# Mabee_WS2812_8bit_V1_1.net
KiCad netlist of a schematic drawn in EAGLE
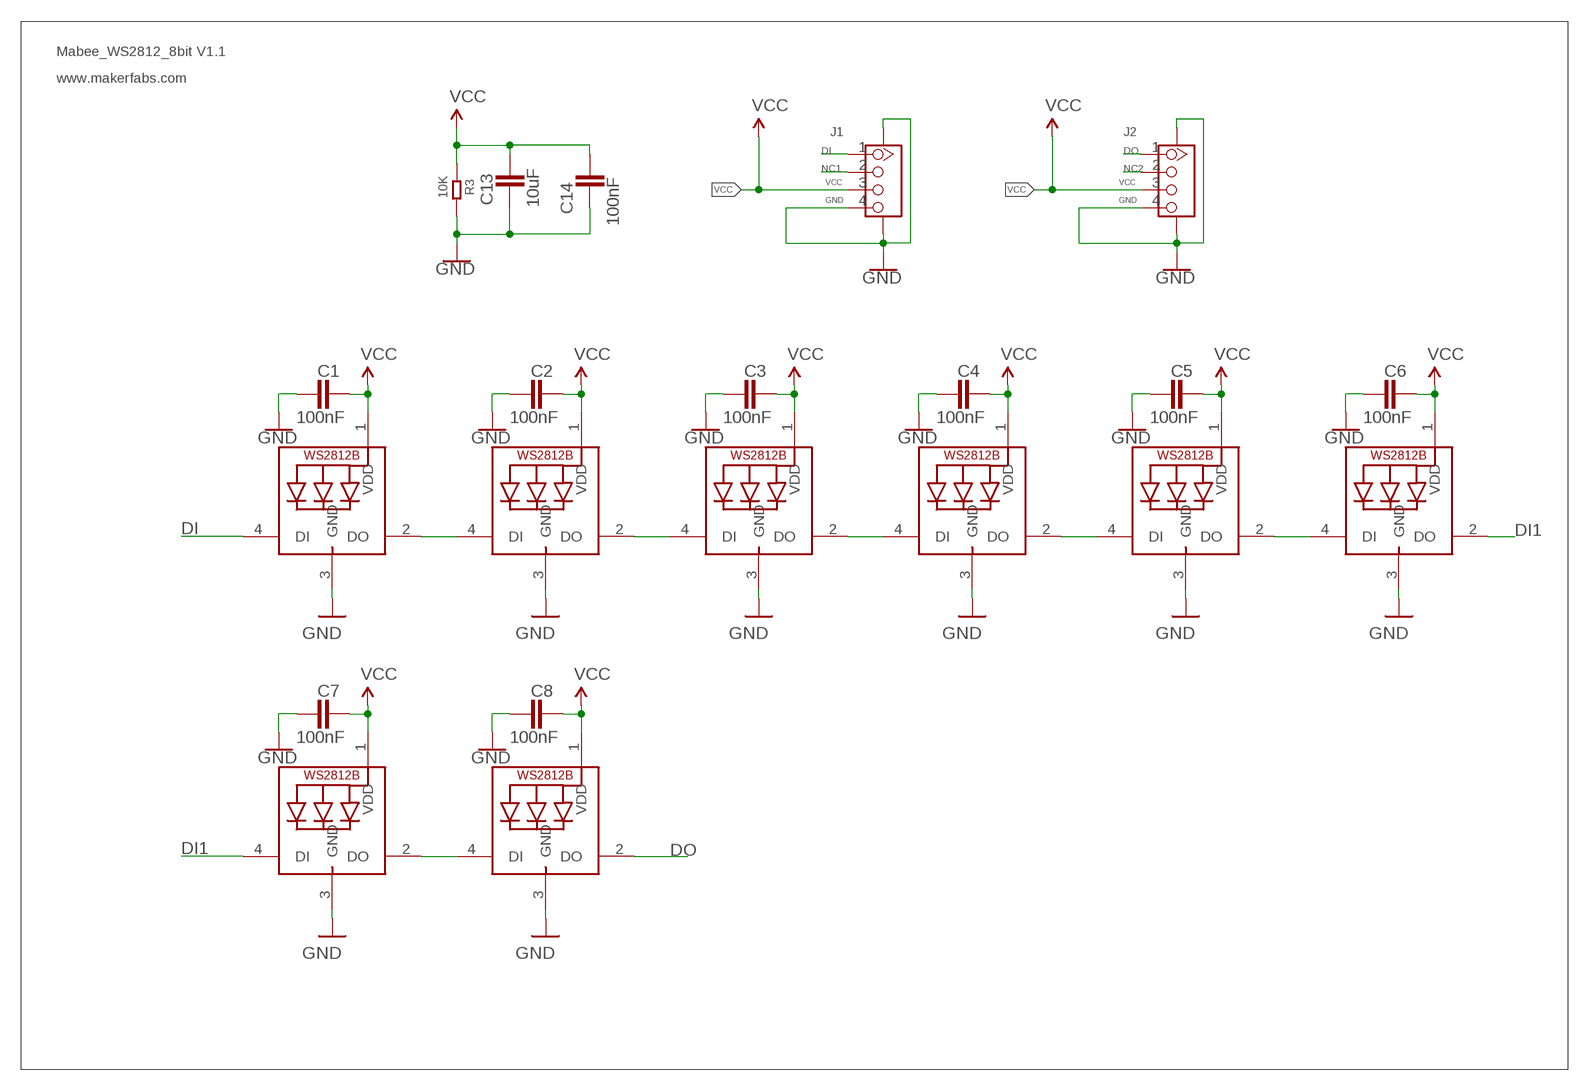
[diagram p0: schematic, sheet 1]

(export (version "E")
  (design (tool "Eeschema 10.0.6"))
  (components
    (comp (ref "C1")
      (value "100nF")
      (footprint "eagle-import:C0603")
      (libsource (lib "eagle-import") (part "C-EUC0603"))
    )
    (comp (ref "C2")
      (value "100nF")
      (footprint "eagle-import:C0603")
      (libsource (lib "eagle-import") (part "C-EUC0603"))
    )
    (comp (ref "C3")
      (value "100nF")
      (footprint "eagle-import:C0603")
      (libsource (lib "eagle-import") (part "C-EUC0603"))
    )
    (comp (ref "C4")
      (value "100nF")
      (footprint "eagle-import:C0603")
      (libsource (lib "eagle-import") (part "C-EUC0603"))
    )
    (comp (ref "C5")
      (value "100nF")
      (footprint "eagle-import:C0603")
      (libsource (lib "eagle-import") (part "C-EUC0603"))
    )
    (comp (ref "C6")
      (value "100nF")
      (footprint "eagle-import:C0603")
      (libsource (lib "eagle-import") (part "C-EUC0603"))
    )
    (comp (ref "C7")
      (value "100nF")
      (footprint "eagle-import:C0603")
      (libsource (lib "eagle-import") (part "C-EUC0603"))
    )
    (comp (ref "C8")
      (value "100nF")
      (footprint "eagle-import:C0603")
      (libsource (lib "eagle-import") (part "C-EUC0603"))
    )
    (comp (ref "C13")
      (value "10uF")
      (footprint "eagle-import:C0603")
      (libsource (lib "eagle-import") (part "C-EUC0603"))
    )
    (comp (ref "C14")
      (value "100nF")
      (footprint "eagle-import:C0603")
      (libsource (lib "eagle-import") (part "C-EUC0603"))
    )
    (comp (ref "J1")
      (value "GROVE-CONNECTOR-SMD'90D'")
      (footprint "eagle-import:HW4-SMD-2.0-90D")
      (libsource (lib "eagle-import") (part "GROVE-CONNECTOR-SMD'90D'"))
    )
    (comp (ref "J2")
      (value "GROVE-CONNECTOR-SMD'90D'")
      (footprint "eagle-import:HW4-SMD-2.0-90D")
      (libsource (lib "eagle-import") (part "GROVE-CONNECTOR-SMD'90D'"))
    )
    (comp (ref "LED0")
      (value "WS2812B3535")
      (footprint "eagle-import:LED3535")
      (libsource (lib "eagle-import") (part "WS2812B3535"))
    )
    (comp (ref "LED1")
      (value "WS2812B3535")
      (footprint "eagle-import:LED3535")
      (libsource (lib "eagle-import") (part "WS2812B3535"))
    )
    (comp (ref "LED2")
      (value "WS2812B3535")
      (footprint "eagle-import:LED3535")
      (libsource (lib "eagle-import") (part "WS2812B3535"))
    )
    (comp (ref "LED3")
      (value "WS2812B3535")
      (footprint "eagle-import:LED3535")
      (libsource (lib "eagle-import") (part "WS2812B3535"))
    )
    (comp (ref "LED4")
      (value "WS2812B3535")
      (footprint "eagle-import:LED3535")
      (libsource (lib "eagle-import") (part "WS2812B3535"))
    )
    (comp (ref "LED5")
      (value "WS2812B3535")
      (footprint "eagle-import:LED3535")
      (libsource (lib "eagle-import") (part "WS2812B3535"))
    )
    (comp (ref "LED6")
      (value "WS2812B3535")
      (footprint "eagle-import:LED3535")
      (libsource (lib "eagle-import") (part "WS2812B3535"))
    )
    (comp (ref "LED7")
      (value "WS2812B3535")
      (footprint "eagle-import:LED3535")
      (libsource (lib "eagle-import") (part "WS2812B3535"))
    )
    (comp (ref "R3")
      (value "10K")
      (footprint "eagle-import:R0603")
      (libsource (lib "eagle-import") (part "R-0603"))
    )
  )
  (nets
    (net (code "1") (name "/DI") (class "Default")
      (node (ref "J1") (pin "1") (pinfunction "1_1") (pintype "bidirectional"))
      (node (ref "LED0") (pin "4") (pinfunction "DI_4") (pintype "input"))
    )
    (net (code "2") (name "/DI1") (class "Default")
      (node (ref "LED5") (pin "2") (pinfunction "DO_2") (pintype "output"))
      (node (ref "LED6") (pin "4") (pinfunction "DI_4") (pintype "input"))
    )
    (net (code "3") (name "/DO") (class "Default")
      (node (ref "J2") (pin "1") (pinfunction "1_1") (pintype "bidirectional"))
      (node (ref "LED7") (pin "2") (pinfunction "DO_2") (pintype "output"))
    )
    (net (code "4") (name "/NC1") (class "Default")
      (node (ref "J1") (pin "2") (pinfunction "2_2") (pintype "bidirectional"))
    )
    (net (code "5") (name "/NC2") (class "Default")
      (node (ref "J2") (pin "2") (pinfunction "2_2") (pintype "bidirectional"))
    )
    (net (code "6") (name "GND") (class "Default")
      (node (ref "C1") (pin "1") (pinfunction "1_1") (pintype "passive"))
      (node (ref "C13") (pin "1") (pinfunction "1_1") (pintype "passive"))
      (node (ref "C14") (pin "1") (pinfunction "1_1") (pintype "passive"))
      (node (ref "C2") (pin "1") (pinfunction "1_1") (pintype "passive"))
      (node (ref "C3") (pin "1") (pinfunction "1_1") (pintype "passive"))
      (node (ref "C4") (pin "1") (pinfunction "1_1") (pintype "passive"))
      (node (ref "C5") (pin "1") (pinfunction "1_1") (pintype "passive"))
      (node (ref "C6") (pin "1") (pinfunction "1_1") (pintype "passive"))
      (node (ref "C7") (pin "1") (pinfunction "1_1") (pintype "passive"))
      (node (ref "C8") (pin "1") (pinfunction "1_1") (pintype "passive"))
      (node (ref "J1") (pin "4") (pinfunction "4_4") (pintype "bidirectional"))
      (node (ref "J1") (pin "SS1") (pinfunction "SS1_SS1") (pintype "bidirectional"))
      (node (ref "J1") (pin "SS2") (pinfunction "SS2_SS2") (pintype "bidirectional"))
      (node (ref "J2") (pin "4") (pinfunction "4_4") (pintype "bidirectional"))
      (node (ref "J2") (pin "SS1") (pinfunction "SS1_SS1") (pintype "bidirectional"))
      (node (ref "J2") (pin "SS2") (pinfunction "SS2_SS2") (pintype "bidirectional"))
      (node (ref "LED0") (pin "3") (pinfunction "GND_3") (pintype "power_in"))
      (node (ref "LED1") (pin "3") (pinfunction "GND_3") (pintype "power_in"))
      (node (ref "LED2") (pin "3") (pinfunction "GND_3") (pintype "power_in"))
      (node (ref "LED3") (pin "3") (pinfunction "GND_3") (pintype "power_in"))
      (node (ref "LED4") (pin "3") (pinfunction "GND_3") (pintype "power_in"))
      (node (ref "LED5") (pin "3") (pinfunction "GND_3") (pintype "power_in"))
      (node (ref "LED6") (pin "3") (pinfunction "GND_3") (pintype "power_in"))
      (node (ref "LED7") (pin "3") (pinfunction "GND_3") (pintype "power_in"))
      (node (ref "R3") (pin "2") (pinfunction "2_2") (pintype "passive"))
    )
    (net (code "7") (name "Net-(LED0-DO)") (class "Default")
      (node (ref "LED0") (pin "2") (pinfunction "DO_2") (pintype "output"))
      (node (ref "LED1") (pin "4") (pinfunction "DI_4") (pintype "input"))
    )
    (net (code "8") (name "Net-(LED1-DO)") (class "Default")
      (node (ref "LED1") (pin "2") (pinfunction "DO_2") (pintype "output"))
      (node (ref "LED2") (pin "4") (pinfunction "DI_4") (pintype "input"))
    )
    (net (code "9") (name "Net-(LED2-DO)") (class "Default")
      (node (ref "LED2") (pin "2") (pinfunction "DO_2") (pintype "output"))
      (node (ref "LED3") (pin "4") (pinfunction "DI_4") (pintype "input"))
    )
    (net (code "10") (name "Net-(LED3-DO)") (class "Default")
      (node (ref "LED3") (pin "2") (pinfunction "DO_2") (pintype "output"))
      (node (ref "LED4") (pin "4") (pinfunction "DI_4") (pintype "input"))
    )
    (net (code "11") (name "Net-(LED4-DO)") (class "Default")
      (node (ref "LED4") (pin "2") (pinfunction "DO_2") (pintype "output"))
      (node (ref "LED5") (pin "4") (pinfunction "DI_4") (pintype "input"))
    )
    (net (code "12") (name "Net-(LED6-DO)") (class "Default")
      (node (ref "LED6") (pin "2") (pinfunction "DO_2") (pintype "output"))
      (node (ref "LED7") (pin "4") (pinfunction "DI_4") (pintype "input"))
    )
    (net (code "13") (name "VCC") (class "Default")
      (node (ref "C1") (pin "2") (pinfunction "2_2") (pintype "passive"))
      (node (ref "C13") (pin "2") (pinfunction "2_2") (pintype "passive"))
      (node (ref "C14") (pin "2") (pinfunction "2_2") (pintype "passive"))
      (node (ref "C2") (pin "2") (pinfunction "2_2") (pintype "passive"))
      (node (ref "C3") (pin "2") (pinfunction "2_2") (pintype "passive"))
      (node (ref "C4") (pin "2") (pinfunction "2_2") (pintype "passive"))
      (node (ref "C5") (pin "2") (pinfunction "2_2") (pintype "passive"))
      (node (ref "C6") (pin "2") (pinfunction "2_2") (pintype "passive"))
      (node (ref "C7") (pin "2") (pinfunction "2_2") (pintype "passive"))
      (node (ref "C8") (pin "2") (pinfunction "2_2") (pintype "passive"))
      (node (ref "J1") (pin "3") (pinfunction "3_3") (pintype "bidirectional"))
      (node (ref "J2") (pin "3") (pinfunction "3_3") (pintype "bidirectional"))
      (node (ref "LED0") (pin "1") (pinfunction "VDD_1") (pintype "power_in"))
      (node (ref "LED1") (pin "1") (pinfunction "VDD_1") (pintype "power_in"))
      (node (ref "LED2") (pin "1") (pinfunction "VDD_1") (pintype "power_in"))
      (node (ref "LED3") (pin "1") (pinfunction "VDD_1") (pintype "power_in"))
      (node (ref "LED4") (pin "1") (pinfunction "VDD_1") (pintype "power_in"))
      (node (ref "LED5") (pin "1") (pinfunction "VDD_1") (pintype "power_in"))
      (node (ref "LED6") (pin "1") (pinfunction "VDD_1") (pintype "power_in"))
      (node (ref "LED7") (pin "1") (pinfunction "VDD_1") (pintype "power_in"))
      (node (ref "R3") (pin "1") (pinfunction "1_1") (pintype "passive"))
    )
  )
)
